# Half_Bridge_Driver.net
KiCad netlist of a schematic drawn in Altium Designer
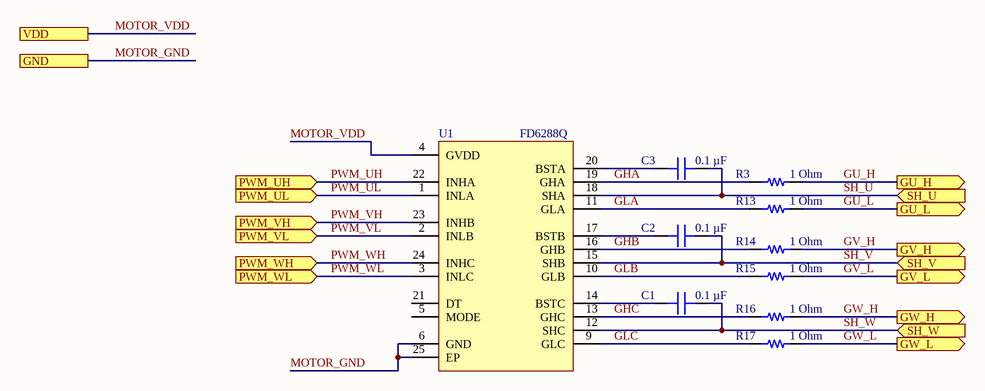
[diagram p0: Half_Bridge_Driver.SchDoc]

(export (version "E")
  (design (tool "Eeschema 10.0.6"))
  (components
    (comp (ref "C1")
      (value "0.1 µF")
      (footprint "CAP 0402_1005")
      (description "CAP CER 0.1UF 16V X7R 0402")
      (fields (field (name "PART NUMBER") "C0402C104K4RACAUTO") (field (name "MANUFACTURER") "KEMET"))
      (libsource (lib "Celestial Altium Library - altium_library") (part "Capacitor"))
    )
    (comp (ref "C2")
      (value "0.1 µF")
      (footprint "CAP 0402_1005")
      (description "CAP CER 0.1UF 16V X7R 0402")
      (fields (field (name "PART NUMBER") "C0402C104K4RACAUTO") (field (name "MANUFACTURER") "KEMET"))
      (libsource (lib "Celestial Altium Library - altium_library") (part "Capacitor"))
    )
    (comp (ref "C3")
      (value "0.1 µF")
      (footprint "CAP 0402_1005")
      (description "CAP CER 0.1UF 16V X7R 0402")
      (fields (field (name "PART NUMBER") "C0402C104K4RACAUTO") (field (name "MANUFACTURER") "KEMET"))
      (libsource (lib "Celestial Altium Library - altium_library") (part "Capacitor"))
    )
    (comp (ref "R3")
      (value "1 Ohm")
      (footprint "RES 0402_1005")
      (description "RES 14.3K OHM 1% 1/10W 0402")
      (fields
        (field (name "PART NUMBER") "RK73H1ETTP1432F")
        (field (name "MANUFACTURER") "KOA Speer Electronics, Inc.")
      )
      (libsource (lib "Celestial Altium Library - altium_library") (part "Resistor"))
    )
    (comp (ref "R13")
      (value "1 Ohm")
      (footprint "RES 0402_1005")
      (description "RES 14.3K OHM 1% 1/10W 0402")
      (fields
        (field (name "PART NUMBER") "RK73H1ETTP1432F")
        (field (name "MANUFACTURER") "KOA Speer Electronics, Inc.")
      )
      (libsource (lib "Celestial Altium Library - altium_library") (part "Resistor"))
    )
    (comp (ref "R14")
      (value "1 Ohm")
      (footprint "RES 0402_1005")
      (description "RES 14.3K OHM 1% 1/10W 0402")
      (fields
        (field (name "PART NUMBER") "RK73H1ETTP1432F")
        (field (name "MANUFACTURER") "KOA Speer Electronics, Inc.")
      )
      (libsource (lib "Celestial Altium Library - altium_library") (part "Resistor"))
    )
    (comp (ref "R15")
      (value "1 Ohm")
      (footprint "RES 0402_1005")
      (description "RES 14.3K OHM 1% 1/10W 0402")
      (fields
        (field (name "PART NUMBER") "RK73H1ETTP1432F")
        (field (name "MANUFACTURER") "KOA Speer Electronics, Inc.")
      )
      (libsource (lib "Celestial Altium Library - altium_library") (part "Resistor"))
    )
    (comp (ref "R16")
      (value "1 Ohm")
      (footprint "RES 0402_1005")
      (description "RES 14.3K OHM 1% 1/10W 0402")
      (fields
        (field (name "PART NUMBER") "RK73H1ETTP1432F")
        (field (name "MANUFACTURER") "KOA Speer Electronics, Inc.")
      )
      (libsource (lib "Celestial Altium Library - altium_library") (part "Resistor"))
    )
    (comp (ref "R17")
      (value "1 Ohm")
      (footprint "RES 0402_1005")
      (description "RES 14.3K OHM 1% 1/10W 0402")
      (fields
        (field (name "PART NUMBER") "RK73H1ETTP1432F")
        (field (name "MANUFACTURER") "KOA Speer Electronics, Inc.")
      )
      (libsource (lib "Celestial Altium Library - altium_library") (part "Resistor"))
    )
    (comp (ref "U1")
      (value "FD6288Q")
      (footprint "QFN50P400X400X100-25N")
      (description "3 Phase Gate Driver 1.5-2.2A")
      (fields (field (name "MF") "Texas Instruments") (field (name "MP") "UCC27282DRCR"))
      (libsource (lib "IC") (part "FD6288Q"))
    )
  )
  (nets
    (net (code "1") (name "/GHA") (class "Default")
      (node (ref "R3") (pin "1") (pinfunction "1_1") (pintype "passive"))
      (node (ref "U1") (pin "19") (pinfunction "GHA_19") (pintype "passive"))
    )
    (net (code "2") (name "/GHB") (class "Default")
      (node (ref "R14") (pin "1") (pinfunction "1_1") (pintype "passive"))
      (node (ref "U1") (pin "16") (pinfunction "GHB_16") (pintype "passive"))
    )
    (net (code "3") (name "/GHC") (class "Default")
      (node (ref "R16") (pin "1") (pinfunction "1_1") (pintype "passive"))
      (node (ref "U1") (pin "13") (pinfunction "GHC_13") (pintype "passive"))
    )
    (net (code "4") (name "/GLA") (class "Default")
      (node (ref "R13") (pin "1") (pinfunction "1_1") (pintype "passive"))
      (node (ref "U1") (pin "11") (pinfunction "GLA_11") (pintype "passive"))
    )
    (net (code "5") (name "/GLB") (class "Default")
      (node (ref "R15") (pin "1") (pinfunction "1_1") (pintype "passive"))
      (node (ref "U1") (pin "10") (pinfunction "GLB_10") (pintype "passive"))
    )
    (net (code "6") (name "/GLC") (class "Default")
      (node (ref "R17") (pin "1") (pinfunction "1_1") (pintype "passive"))
      (node (ref "U1") (pin "9") (pinfunction "GLC_9") (pintype "passive"))
    )
    (net (code "7") (name "/GU_H") (class "Default")
      (node (ref "R3") (pin "2") (pinfunction "2_2") (pintype "passive"))
    )
    (net (code "8") (name "/GU_L") (class "Default")
      (node (ref "R13") (pin "2") (pinfunction "2_2") (pintype "passive"))
    )
    (net (code "9") (name "/GV_H") (class "Default")
      (node (ref "R14") (pin "2") (pinfunction "2_2") (pintype "passive"))
    )
    (net (code "10") (name "/GV_L") (class "Default")
      (node (ref "R15") (pin "2") (pinfunction "2_2") (pintype "passive"))
    )
    (net (code "11") (name "/GW_H") (class "Default")
      (node (ref "R16") (pin "2") (pinfunction "2_2") (pintype "passive"))
    )
    (net (code "12") (name "/GW_L") (class "Default")
      (node (ref "R17") (pin "2") (pinfunction "2_2") (pintype "passive"))
    )
    (net (code "13") (name "/MOTOR_GND") (class "Default")
      (node (ref "U1") (pin "25") (pinfunction "EP_25") (pintype "passive"))
      (node (ref "U1") (pin "6") (pinfunction "GND_6") (pintype "passive"))
    )
    (net (code "14") (name "/MOTOR_VDD") (class "Default")
      (node (ref "U1") (pin "4") (pinfunction "GVDD_4") (pintype "passive"))
    )
    (net (code "15") (name "/PWM_UH") (class "Default")
      (node (ref "U1") (pin "22") (pinfunction "INHA_22") (pintype "passive"))
    )
    (net (code "16") (name "/PWM_UL") (class "Default")
      (node (ref "U1") (pin "1") (pinfunction "INLA_1") (pintype "passive"))
    )
    (net (code "17") (name "/PWM_VH") (class "Default")
      (node (ref "U1") (pin "23") (pinfunction "INHB_23") (pintype "passive"))
    )
    (net (code "18") (name "/PWM_VL") (class "Default")
      (node (ref "U1") (pin "2") (pinfunction "INLB_2") (pintype "passive"))
    )
    (net (code "19") (name "/PWM_WH") (class "Default")
      (node (ref "U1") (pin "24") (pinfunction "INHC_24") (pintype "passive"))
    )
    (net (code "20") (name "/PWM_WL") (class "Default")
      (node (ref "U1") (pin "3") (pinfunction "INLC_3") (pintype "passive"))
    )
    (net (code "21") (name "/SH_U") (class "Default")
      (node (ref "C3") (pin "2") (pinfunction "2_2") (pintype "passive"))
      (node (ref "U1") (pin "18") (pinfunction "SHA_18") (pintype "passive"))
    )
    (net (code "22") (name "/SH_V") (class "Default")
      (node (ref "C2") (pin "2") (pinfunction "2_2") (pintype "passive"))
      (node (ref "U1") (pin "15") (pinfunction "SHB_15") (pintype "passive"))
    )
    (net (code "23") (name "/SH_W") (class "Default")
      (node (ref "C1") (pin "2") (pinfunction "2_2") (pintype "passive"))
      (node (ref "U1") (pin "12") (pinfunction "SHC_12") (pintype "passive"))
    )
    (net (code "24") (name "Net-(U1-BSTA)") (class "Default")
      (node (ref "C3") (pin "1") (pinfunction "1_1") (pintype "passive"))
      (node (ref "U1") (pin "20") (pinfunction "BSTA_20") (pintype "passive"))
    )
    (net (code "25") (name "Net-(U1-BSTB)") (class "Default")
      (node (ref "C2") (pin "1") (pinfunction "1_1") (pintype "passive"))
      (node (ref "U1") (pin "17") (pinfunction "BSTB_17") (pintype "passive"))
    )
    (net (code "26") (name "Net-(U1-BSTC)") (class "Default")
      (node (ref "C1") (pin "1") (pinfunction "1_1") (pintype "passive"))
      (node (ref "U1") (pin "14") (pinfunction "BSTC_14") (pintype "passive"))
    )
    (net (code "27") (name "unconnected-(U1-DT-Pad21)") (class "Default")
      (node (ref "U1") (pin "21") (pinfunction "DT_21") (pintype "passive"))
    )
    (net (code "28") (name "unconnected-(U1-MODE-Pad5)") (class "Default")
      (node (ref "U1") (pin "5") (pinfunction "MODE_5") (pintype "passive"))
    )
  )
)
